# ADB-3020-CDV.net
KiCad netlist of a schematic drawn in EAGLE
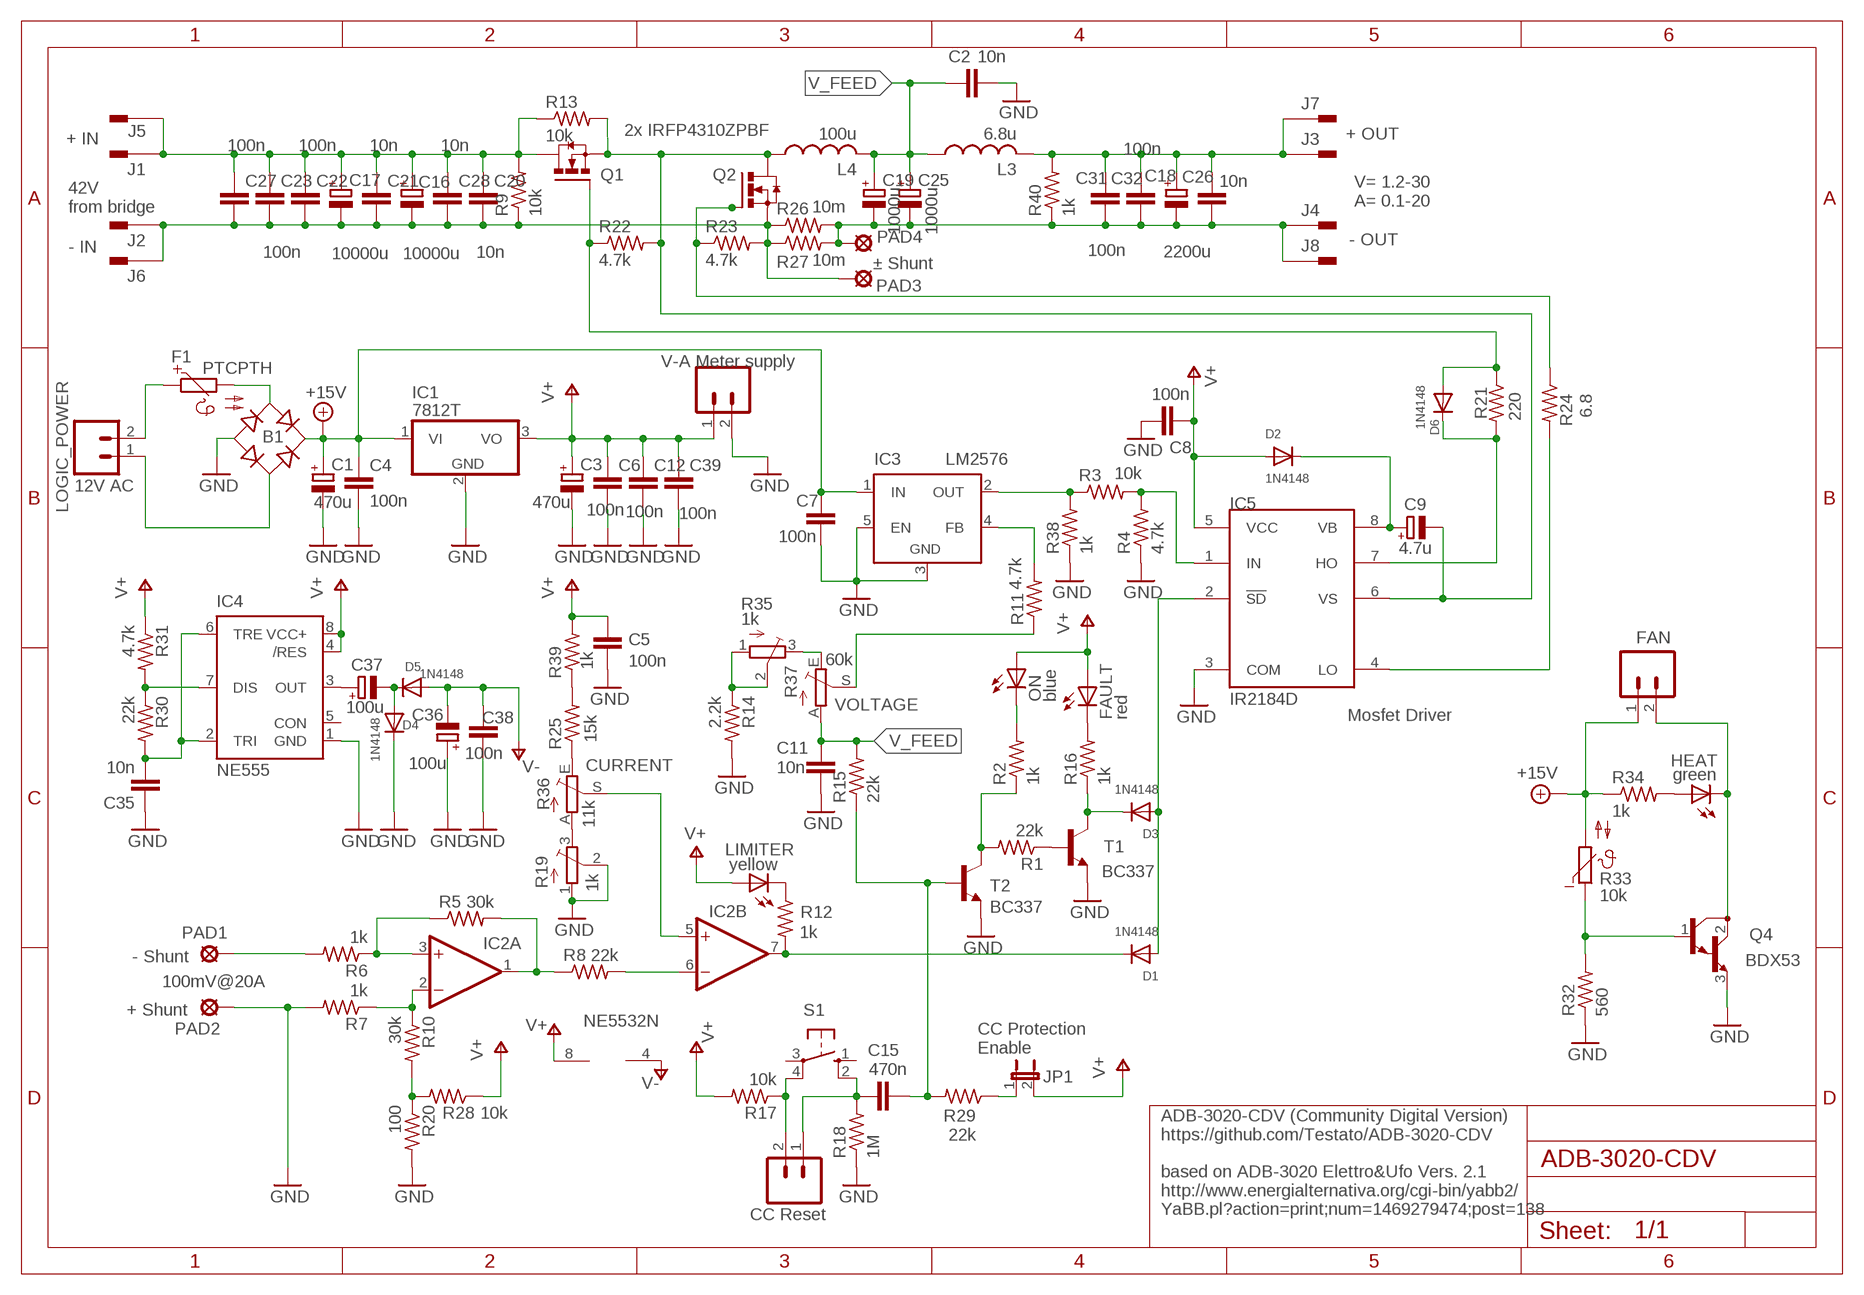
[diagram p0: schematic, sheet 1]

(export (version "E")
  (design (tool "Eeschema 10.0.6"))
  (components
    (comp (ref "B1")
      (value "RECTIFIER-RB1A")
      (footprint "eagle-import:RB1A")
      (libsource (lib "eagle-import") (part "RECTIFIER-RB1A"))
    )
    (comp (ref "C1")
      (value "470u")
      (footprint "eagle-import:E2-5")
      (libsource (lib "eagle-import") (part "CPOL-EUE2-5"))
    )
    (comp (ref "C2")
      (value "10n")
      (footprint "eagle-import:C2.5-2")
      (libsource (lib "eagle-import") (part "C2.5/2"))
    )
    (comp (ref "C3")
      (value "470u")
      (footprint "eagle-import:E2-5")
      (libsource (lib "eagle-import") (part "CPOL-EUE2-5"))
    )
    (comp (ref "C4")
      (value "100n")
      (footprint "eagle-import:C2.5-2")
      (libsource (lib "eagle-import") (part "C2.5/2"))
    )
    (comp (ref "C5")
      (value "100n")
      (footprint "eagle-import:C2.5-2")
      (libsource (lib "eagle-import") (part "C2.5/2"))
    )
    (comp (ref "C6")
      (value "100n")
      (footprint "eagle-import:C2.5-2")
      (libsource (lib "eagle-import") (part "C2.5/2"))
    )
    (comp (ref "C7")
      (value "100n")
      (footprint "eagle-import:C2.5-2")
      (libsource (lib "eagle-import") (part "C2.5/2"))
    )
    (comp (ref "C8")
      (value "100n")
      (footprint "eagle-import:C2.5-2")
      (libsource (lib "eagle-import") (part "C2.5/2"))
    )
    (comp (ref "C9")
      (value "4.7u")
      (footprint "eagle-import:E2-5")
      (libsource (lib "eagle-import") (part "CPOL-EUE2-5"))
    )
    (comp (ref "C11")
      (value "10n")
      (footprint "eagle-import:C2.5-2")
      (libsource (lib "eagle-import") (part "C2.5/2"))
    )
    (comp (ref "C12")
      (value "100n")
      (footprint "eagle-import:C2.5-2")
      (libsource (lib "eagle-import") (part "C2.5/2"))
    )
    (comp (ref "C15")
      (value "470n")
      (footprint "eagle-import:C2.5-2")
      (libsource (lib "eagle-import") (part "C2.5/2"))
    )
    (comp (ref "C16")
      (value "10000u")
      (footprint "eagle-import:E2-5")
      (libsource (lib "eagle-import") (part "CPOL-EUE2-5"))
    )
    (comp (ref "C17")
      (value "10000u")
      (footprint "eagle-import:E2-5")
      (libsource (lib "eagle-import") (part "CPOL-EUE2-5"))
    )
    (comp (ref "C18")
      (value "2200u")
      (footprint "eagle-import:E2-5")
      (libsource (lib "eagle-import") (part "CPOL-EUE2-5"))
    )
    (comp (ref "C19")
      (value "1000u")
      (footprint "eagle-import:E2-5")
      (libsource (lib "eagle-import") (part "CPOL-EUE2-5"))
    )
    (comp (ref "C20")
      (value "10n")
      (footprint "eagle-import:C2.5-2")
      (libsource (lib "eagle-import") (part "C2.5/2"))
    )
    (comp (ref "C21")
      (value "10n")
      (footprint "eagle-import:C2.5-2")
      (libsource (lib "eagle-import") (part "C2.5/2"))
    )
    (comp (ref "C22")
      (value "100n")
      (footprint "eagle-import:C2.5-2")
      (libsource (lib "eagle-import") (part "C2.5/2"))
    )
    (comp (ref "C23")
      (value "100n")
      (footprint "eagle-import:C2.5-2")
      (libsource (lib "eagle-import") (part "C2.5/2"))
    )
    (comp (ref "C25")
      (value "1000u")
      (footprint "eagle-import:E2-5")
      (libsource (lib "eagle-import") (part "CPOL-EUE2-5"))
    )
    (comp (ref "C26")
      (value "10n")
      (footprint "eagle-import:C2.5-2")
      (libsource (lib "eagle-import") (part "C2.5/2"))
    )
    (comp (ref "C27")
      (value "100n")
      (footprint "eagle-import:C2.5-2")
      (libsource (lib "eagle-import") (part "C2.5/2"))
    )
    (comp (ref "C28")
      (value "10n")
      (footprint "eagle-import:C2.5-2")
      (libsource (lib "eagle-import") (part "C2.5/2"))
    )
    (comp (ref "C31")
      (value "100n")
      (footprint "eagle-import:C2.5-2")
      (libsource (lib "eagle-import") (part "C2.5/2"))
    )
    (comp (ref "C32")
      (value "100n")
      (footprint "eagle-import:C2.5-2")
      (libsource (lib "eagle-import") (part "C2.5/2"))
    )
    (comp (ref "C35")
      (value "10n")
      (footprint "eagle-import:C2.5-2")
      (libsource (lib "eagle-import") (part "C2.5/2"))
    )
    (comp (ref "C36")
      (value "100u")
      (footprint "eagle-import:E2-5")
      (libsource (lib "eagle-import") (part "CPOL-EUE2-5"))
    )
    (comp (ref "C37")
      (value "100u")
      (footprint "eagle-import:E2-5")
      (libsource (lib "eagle-import") (part "CPOL-EUE2-5"))
    )
    (comp (ref "C38")
      (value "100n")
      (footprint "eagle-import:C2.5-2")
      (libsource (lib "eagle-import") (part "C2.5/2"))
    )
    (comp (ref "C39")
      (value "100n")
      (footprint "eagle-import:C2.5-2")
      (libsource (lib "eagle-import") (part "C2.5/2"))
    )
    (comp (ref "D1")
      (value "1N4148")
      (footprint "eagle-import:DO-1N4148")
      (libsource (lib "eagle-import") (part "DIODEDO-1N4148"))
    )
    (comp (ref "D2")
      (value "1N4148")
      (footprint "eagle-import:DO-1N4148")
      (libsource (lib "eagle-import") (part "DIODEDO-1N4148"))
    )
    (comp (ref "D3")
      (value "1N4148")
      (footprint "eagle-import:DO-1N4148")
      (libsource (lib "eagle-import") (part "DIODEDO-1N4148"))
    )
    (comp (ref "D4")
      (value "1N4148")
      (footprint "eagle-import:DO-1N4148")
      (libsource (lib "eagle-import") (part "DIODEDO-1N4148"))
    )
    (comp (ref "D5")
      (value "1N4148")
      (footprint "eagle-import:DO-1N4148")
      (libsource (lib "eagle-import") (part "DIODEDO-1N4148"))
    )
    (comp (ref "D6")
      (value "1N4148")
      (footprint "eagle-import:DO-1N4148")
      (libsource (lib "eagle-import") (part "DIODEDO-1N4148"))
    )
    (comp (ref "F1")
      (value "PTCPTH")
      (footprint "eagle-import:P660")
      (libsource (lib "eagle-import") (part "PTC660"))
    )
    (comp (ref "FAN")
      (value "fan")
      (footprint "eagle-import:02PA")
      (libsource (lib "eagle-import") (part "MA02"))
    )
    (comp (ref "FAULT")
      (value "red")
      (footprint "eagle-import:LED3MM")
      (libsource (lib "eagle-import") (part "LED3MM"))
    )
    (comp (ref "HEAT")
      (value "green")
      (footprint "eagle-import:LED3MM")
      (libsource (lib "eagle-import") (part "LED3MM"))
    )
    (comp (ref "IC1")
      (value "7812T")
      (footprint "eagle-import:TO220H")
      (libsource (lib "eagle-import") (part "78T12"))
    )
    (comp (ref "IC2")
      (value "NE5532N")
      (footprint "eagle-import:DIL08")
      (libsource (lib "eagle-import") (part "NE5532N"))
    )
    (comp (ref "IC3")
      (value "LM2576")
      (footprint "eagle-import:TO220-52")
      (libsource (lib "eagle-import") (part "LM2596TH"))
    )
    (comp (ref "IC4")
      (value "NE555")
      (footprint "eagle-import:DIL-08")
      (fields (field (name "MF") "Arrow Electronics") (field (name "MPN") "NE555N"))
      (libsource (lib "eagle-import") (part "NE555"))
    )
    (comp (ref "IC5")
      (value "IR2184D")
      (footprint "eagle-import:DIL08")
      (libsource (lib "eagle-import") (part "IR2184D"))
    )
    (comp (ref "J1")
      (value "+ IN")
      (footprint "eagle-import:F061.040")
      (libsource (lib "eagle-import") (part "PIN2F061.040"))
    )
    (comp (ref "J2")
      (value "- IN")
      (footprint "eagle-import:F061.040")
      (libsource (lib "eagle-import") (part "PIN2F061.040"))
    )
    (comp (ref "J3")
      (value "+ OUT")
      (footprint "eagle-import:F061.040")
      (libsource (lib "eagle-import") (part "PIN2F061.040"))
    )
    (comp (ref "J4")
      (value "PIN2F061.040")
      (footprint "eagle-import:F061.040")
      (libsource (lib "eagle-import") (part "PIN2F061.040"))
    )
    (comp (ref "J5")
      (value "+ IN")
      (footprint "eagle-import:F061.040")
      (libsource (lib "eagle-import") (part "PIN2F061.040"))
    )
    (comp (ref "J6")
      (value "- IN")
      (footprint "eagle-import:F061.040")
      (libsource (lib "eagle-import") (part "PIN2F061.040"))
    )
    (comp (ref "J7")
      (value "PIN2F061.040")
      (footprint "eagle-import:F061.040")
      (libsource (lib "eagle-import") (part "PIN2F061.040"))
    )
    (comp (ref "J8")
      (value "- OUT")
      (footprint "eagle-import:F061.040")
      (libsource (lib "eagle-import") (part "PIN2F061.040"))
    )
    (comp (ref "JP1")
      (value "jp1")
      (footprint "eagle-import:JP1")
      (libsource (lib "eagle-import") (part "JP1E"))
    )
    (comp (ref "L3")
      (value "6.8u")
      (footprint "eagle-import:6000")
      (libsource (lib "eagle-import") (part "L"))
    )
    (comp (ref "L4")
      (value "100u")
      (footprint "eagle-import:6000")
      (libsource (lib "eagle-import") (part "L"))
    )
    (comp (ref "LIMITER")
      (value "yellow")
      (footprint "eagle-import:LED3MM")
      (libsource (lib "eagle-import") (part "LED3MM"))
    )
    (comp (ref "LOGIC_POWER")
      (value "12V AC")
      (footprint "eagle-import:02PA")
      (libsource (lib "eagle-import") (part "MA02"))
    )
    (comp (ref "ON")
      (value "blue")
      (footprint "eagle-import:LED3MM")
      (libsource (lib "eagle-import") (part "LED3MM"))
    )
    (comp (ref "PAD1")
      (value "LSP13")
      (footprint "eagle-import:LSP13")
      (libsource (lib "eagle-import") (part "LSP13"))
    )
    (comp (ref "PAD2")
      (value "LSP13")
      (footprint "eagle-import:LSP13")
      (libsource (lib "eagle-import") (part "LSP13"))
    )
    (comp (ref "PAD3")
      (value "LSP13")
      (footprint "eagle-import:LSP13")
      (libsource (lib "eagle-import") (part "LSP13"))
    )
    (comp (ref "PAD4")
      (value "LSP13")
      (footprint "eagle-import:LSP13")
      (libsource (lib "eagle-import") (part "LSP13"))
    )
    (comp (ref "Q1")
      (value "IRFP240-H")
      (footprint "eagle-import:TO247BH")
      (libsource (lib "eagle-import") (part "IRFP240-H"))
    )
    (comp (ref "Q2")
      (value "IRFP240-H")
      (footprint "eagle-import:TO247BH")
      (libsource (lib "eagle-import") (part "IRFP240-H"))
    )
    (comp (ref "Q4")
      (value "BDX53")
      (footprint "eagle-import:TO220")
      (libsource (lib "eagle-import") (part "BDX53"))
    )
    (comp (ref "R1")
      (value "22k")
      (footprint "eagle-import:0204_5")
      (libsource (lib "eagle-import") (part "R-US_0204/5"))
    )
    (comp (ref "R2")
      (value "1k")
      (footprint "eagle-import:0204_5")
      (libsource (lib "eagle-import") (part "R-US_0204/5"))
    )
    (comp (ref "R3")
      (value "10k")
      (footprint "eagle-import:0204_5")
      (libsource (lib "eagle-import") (part "R-US_0204/5"))
    )
    (comp (ref "R4")
      (value "4.7k")
      (footprint "eagle-import:0204_5")
      (libsource (lib "eagle-import") (part "R-US_0204/5"))
    )
    (comp (ref "R5")
      (value "30k")
      (footprint "eagle-import:0204_5")
      (libsource (lib "eagle-import") (part "R-US_0204/5"))
    )
    (comp (ref "R6")
      (value "1k")
      (footprint "eagle-import:0204_5")
      (libsource (lib "eagle-import") (part "R-US_0204/5"))
    )
    (comp (ref "R7")
      (value "1k")
      (footprint "eagle-import:0204_5")
      (libsource (lib "eagle-import") (part "R-US_0204/5"))
    )
    (comp (ref "R8")
      (value "22k")
      (footprint "eagle-import:0204_5")
      (libsource (lib "eagle-import") (part "R-US_0204/5"))
    )
    (comp (ref "R9")
      (value "10k")
      (footprint "eagle-import:0204_5")
      (libsource (lib "eagle-import") (part "R-US_0204/5"))
    )
    (comp (ref "R10")
      (value "30k")
      (footprint "eagle-import:0204_5")
      (libsource (lib "eagle-import") (part "R-US_0204/5"))
    )
    (comp (ref "R11")
      (value "4.7k")
      (footprint "eagle-import:0204_5")
      (libsource (lib "eagle-import") (part "R-US_0204/5"))
    )
    (comp (ref "R12")
      (value "1k")
      (footprint "eagle-import:0204_5")
      (libsource (lib "eagle-import") (part "R-US_0204/5"))
    )
    (comp (ref "R13")
      (value "10k")
      (footprint "eagle-import:0204_5")
      (libsource (lib "eagle-import") (part "R-US_0204/5"))
    )
    (comp (ref "R14")
      (value "2.2k")
      (footprint "eagle-import:0204_5")
      (libsource (lib "eagle-import") (part "R-US_0204/5"))
    )
    (comp (ref "R15")
      (value "22k")
      (footprint "eagle-import:0204_5")
      (libsource (lib "eagle-import") (part "R-US_0204/5"))
    )
    (comp (ref "R16")
      (value "1k")
      (footprint "eagle-import:0204_5")
      (libsource (lib "eagle-import") (part "R-US_0204/5"))
    )
    (comp (ref "R17")
      (value "10k")
      (footprint "eagle-import:0204_5")
      (libsource (lib "eagle-import") (part "R-US_0204/5"))
    )
    (comp (ref "R18")
      (value "1M")
      (footprint "eagle-import:0204_5")
      (libsource (lib "eagle-import") (part "R-US_0204/5"))
    )
    (comp (ref "R19")
      (value "1k")
      (footprint "eagle-import:TRIM-3386")
      (libsource (lib "eagle-import") (part "TRIMPOT3386"))
    )
    (comp (ref "R20")
      (value "100")
      (footprint "eagle-import:0204_5")
      (libsource (lib "eagle-import") (part "R-US_0204/5"))
    )
    (comp (ref "R21")
      (value "220")
      (footprint "eagle-import:0204_5")
      (libsource (lib "eagle-import") (part "R-US_0204/5"))
    )
    (comp (ref "R22")
      (value "4.7k")
      (footprint "eagle-import:0204_5")
      (libsource (lib "eagle-import") (part "R-US_0204/5"))
    )
    (comp (ref "R23")
      (value "4.7k")
      (footprint "eagle-import:0204_5")
      (libsource (lib "eagle-import") (part "R-US_0204/5"))
    )
    (comp (ref "R24")
      (value "6.8")
      (footprint "eagle-import:0204_5")
      (libsource (lib "eagle-import") (part "R-US_0204/5"))
    )
    (comp (ref "R25")
      (value "15k")
      (footprint "eagle-import:0204_5")
      (libsource (lib "eagle-import") (part "R-US_0204/5"))
    )
    (comp (ref "R26")
      (value "10m")
      (footprint "eagle-import:0204_5")
      (libsource (lib "eagle-import") (part "R-US_0204/5"))
    )
    (comp (ref "R27")
      (value "10m")
      (footprint "eagle-import:0204_5")
      (libsource (lib "eagle-import") (part "R-US_0204/5"))
    )
    (comp (ref "R28")
      (value "10k")
      (footprint "eagle-import:0204_5")
      (libsource (lib "eagle-import") (part "R-US_0204/5"))
    )
    (comp (ref "R29")
      (value "22k")
      (footprint "eagle-import:0204_5")
      (libsource (lib "eagle-import") (part "R-US_0204/5"))
    )
    (comp (ref "R30")
      (value "22k")
      (footprint "eagle-import:0204_5")
      (libsource (lib "eagle-import") (part "R-US_0204/5"))
    )
    (comp (ref "R31")
      (value "4.7k")
      (footprint "eagle-import:0204_5")
      (libsource (lib "eagle-import") (part "R-US_0204/5"))
    )
    (comp (ref "R32")
      (value "560")
      (footprint "eagle-import:0204_5")
      (libsource (lib "eagle-import") (part "R-US_0204/5"))
    )
    (comp (ref "R33")
      (value "10k")
      (footprint "eagle-import:P640")
      (libsource (lib "eagle-import") (part "NTC640"))
    )
    (comp (ref "R34")
      (value "1k")
      (footprint "eagle-import:0204_5")
      (libsource (lib "eagle-import") (part "R-US_0204/5"))
    )
    (comp (ref "R35")
      (value "1k")
      (footprint "eagle-import:TRIM-3386")
      (libsource (lib "eagle-import") (part "TRIMPOT3386"))
    )
    (comp (ref "R36")
      (value "11k")
      (footprint "eagle-import:S64YW")
      (libsource (lib "eagle-import") (part "TRIM_1234-S64YW"))
    )
    (comp (ref "R37")
      (value "60k")
      (footprint "eagle-import:S64YW")
      (libsource (lib "eagle-import") (part "TRIM_1234-S64YW"))
    )
    (comp (ref "R38")
      (value "1k")
      (footprint "eagle-import:0204_5")
      (libsource (lib "eagle-import") (part "R-US_0204/5"))
    )
    (comp (ref "R39")
      (value "1k")
      (footprint "eagle-import:0204_5")
      (libsource (lib "eagle-import") (part "R-US_0204/5"))
    )
    (comp (ref "R40")
      (value "1k")
      (footprint "eagle-import:0204_5")
      (libsource (lib "eagle-import") (part "R-US_0204/5"))
    )
    (comp (ref "RESET")
      (value "CC Reset")
      (footprint "eagle-import:02PA")
      (libsource (lib "eagle-import") (part "MA02"))
    )
    (comp (ref "S1")
      (value "CC Reset")
      (footprint "eagle-import:B3F-40XX")
      (fields (field (name "MF") "OMRON COMPONENTS USA") (field (name "MPN") "B3F-4000"))
      (libsource (lib "eagle-import") (part "40-XX"))
    )
    (comp (ref "T1")
      (value "BC337")
      (footprint "eagle-import:TO92")
      (libsource (lib "eagle-import") (part "BC337"))
    )
    (comp (ref "T2")
      (value "BC337")
      (footprint "eagle-import:TO92")
      (libsource (lib "eagle-import") (part "BC337"))
    )
    (comp (ref "V-A_METER_SUPPLY")
      (value "V-A Meter supply")
      (footprint "eagle-import:02PA")
      (libsource (lib "eagle-import") (part "MA02"))
    )
  )
  (nets
    (net (code "1") (name "+15V") (class "Default")
      (node (ref "B1") (pin "+") (pinfunction "+_+") (pintype "passive"))
      (node (ref "C1") (pin "+") (pinfunction "+_+") (pintype "passive"))
      (node (ref "C4") (pin "1") (pinfunction "1_1") (pintype "passive"))
      (node (ref "C7") (pin "1") (pinfunction "1_1") (pintype "passive"))
      (node (ref "FAN") (pin "1") (pinfunction "1_1") (pintype "passive"))
      (node (ref "IC1") (pin "1") (pinfunction "VI_1") (pintype "input"))
      (node (ref "IC3") (pin "1") (pinfunction "IN_1") (pintype "input"))
      (node (ref "R33") (pin "2") (pinfunction "2_2") (pintype "passive"))
      (node (ref "R34") (pin "1") (pinfunction "1_1") (pintype "passive"))
    )
    (net (code "2") (name "GND") (class "Default")
      (node (ref "B1") (pin "-") (pinfunction "-_-") (pintype "passive"))
      (node (ref "C1") (pin "-") (pinfunction "-_-") (pintype "passive"))
      (node (ref "C11") (pin "2") (pinfunction "2_2") (pintype "passive"))
      (node (ref "C12") (pin "2") (pinfunction "2_2") (pintype "passive"))
      (node (ref "C2") (pin "2") (pinfunction "2_2") (pintype "passive"))
      (node (ref "C3") (pin "-") (pinfunction "-_-") (pintype "passive"))
      (node (ref "C35") (pin "1") (pinfunction "1_1") (pintype "passive"))
      (node (ref "C36") (pin "+") (pinfunction "+_+") (pintype "passive"))
      (node (ref "C38") (pin "1") (pinfunction "1_1") (pintype "passive"))
      (node (ref "C39") (pin "2") (pinfunction "2_2") (pintype "passive"))
      (node (ref "C4") (pin "2") (pinfunction "2_2") (pintype "passive"))
      (node (ref "C5") (pin "1") (pinfunction "1_1") (pintype "passive"))
      (node (ref "C6") (pin "2") (pinfunction "2_2") (pintype "passive"))
      (node (ref "C7") (pin "2") (pinfunction "2_2") (pintype "passive"))
      (node (ref "C8") (pin "2") (pinfunction "2_2") (pintype "passive"))
      (node (ref "D4") (pin "C") (pinfunction "C_C") (pintype "passive"))
      (node (ref "IC1") (pin "2") (pinfunction "GND_2") (pintype "passive"))
      (node (ref "IC3") (pin "3") (pinfunction "GND_3") (pintype "power_in"))
      (node (ref "IC3") (pin "5") (pinfunction "EN_5") (pintype "input"))
      (node (ref "IC4") (pin "1") (pinfunction "GND_1") (pintype "power_in"))
      (node (ref "IC5") (pin "3") (pinfunction "COM_3") (pintype "power_in"))
      (node (ref "PAD2") (pin "MP") (pinfunction "MP_MP") (pintype "passive"))
      (node (ref "Q4") (pin "3") (pinfunction "E_3") (pintype "passive"))
      (node (ref "R14") (pin "2") (pinfunction "2_2") (pintype "passive"))
      (node (ref "R18") (pin "1") (pinfunction "1_1") (pintype "passive"))
      (node (ref "R19") (pin "1") (pinfunction "A_1") (pintype "passive"))
      (node (ref "R19") (pin "2") (pinfunction "S_2") (pintype "passive"))
      (node (ref "R20") (pin "2") (pinfunction "2_2") (pintype "passive"))
      (node (ref "R32") (pin "1") (pinfunction "1_1") (pintype "passive"))
      (node (ref "R38") (pin "1") (pinfunction "1_1") (pintype "passive"))
      (node (ref "R4") (pin "1") (pinfunction "1_1") (pintype "passive"))
      (node (ref "R7") (pin "2") (pinfunction "2_2") (pintype "passive"))
      (node (ref "T1") (pin "1") (pinfunction "E_1") (pintype "passive"))
      (node (ref "T2") (pin "1") (pinfunction "E_1") (pintype "passive"))
      (node (ref "V-A_METER_SUPPLY") (pin "2") (pinfunction "2_2") (pintype "passive"))
    )
    (net (code "3") (name "Net-(B1-PadAC1)") (class "Default")
      (node (ref "B1") (pin "AC1") (pinfunction "AC1_AC1") (pintype "passive"))
      (node (ref "F1") (pin "2") (pinfunction "2_2") (pintype "passive"))
    )
    (net (code "4") (name "Net-(B1-PadAC2)") (class "Default")
      (node (ref "B1") (pin "AC2") (pinfunction "AC2_AC2") (pintype "passive"))
      (node (ref "LOGIC_POWER") (pin "1") (pinfunction "1_1") (pintype "passive"))
    )
    (net (code "5") (name "Net-(C16-Pad+)") (class "Default")
      (node (ref "C16") (pin "+") (pinfunction "+_+") (pintype "passive"))
      (node (ref "C17") (pin "+") (pinfunction "+_+") (pintype "passive"))
      (node (ref "C20") (pin "1") (pinfunction "1_1") (pintype "passive"))
      (node (ref "C21") (pin "1") (pinfunction "1_1") (pintype "passive"))
      (node (ref "C22") (pin "1") (pinfunction "1_1") (pintype "passive"))
      (node (ref "C23") (pin "1") (pinfunction "1_1") (pintype "passive"))
      (node (ref "C27") (pin "1") (pinfunction "1_1") (pintype "passive"))
      (node (ref "C28") (pin "1") (pinfunction "1_1") (pintype "passive"))
      (node (ref "J1") (pin "A1") (pinfunction "1_A1") (pintype "passive"))
      (node (ref "J1") (pin "A2") (pinfunction "1_A2") (pintype "passive"))
      (node (ref "J5") (pin "A1") (pinfunction "1_A1") (pintype "passive"))
      (node (ref "J5") (pin "A2") (pinfunction "1_A2") (pintype "passive"))
      (node (ref "Q1") (pin "D") (pinfunction "D_D") (pintype "passive"))
      (node (ref "R13") (pin "1") (pinfunction "1_1") (pintype "passive"))
      (node (ref "R9") (pin "2") (pinfunction "2_2") (pintype "passive"))
    )
    (net (code "6") (name "Net-(C16-Pad-)") (class "Default")
      (node (ref "C16") (pin "-") (pinfunction "-_-") (pintype "passive"))
      (node (ref "C17") (pin "-") (pinfunction "-_-") (pintype "passive"))
      (node (ref "C20") (pin "2") (pinfunction "2_2") (pintype "passive"))
      (node (ref "C21") (pin "2") (pinfunction "2_2") (pintype "passive"))
      (node (ref "C22") (pin "2") (pinfunction "2_2") (pintype "passive"))
      (node (ref "C23") (pin "2") (pinfunction "2_2") (pintype "passive"))
      (node (ref "C27") (pin "2") (pinfunction "2_2") (pintype "passive"))
      (node (ref "C28") (pin "2") (pinfunction "2_2") (pintype "passive"))
      (node (ref "J2") (pin "A1") (pinfunction "1_A1") (pintype "passive"))
      (node (ref "J2") (pin "A2") (pinfunction "1_A2") (pintype "passive"))
      (node (ref "J6") (pin "A1") (pinfunction "1_A1") (pintype "passive"))
      (node (ref "J6") (pin "A2") (pinfunction "1_A2") (pintype "passive"))
      (node (ref "PAD3") (pin "MP") (pinfunction "MP_MP") (pintype "passive"))
      (node (ref "Q2") (pin "S") (pinfunction "S_S") (pintype "passive"))
      (node (ref "R23") (pin "2") (pinfunction "2_2") (pintype "passive"))
      (node (ref "R26") (pin "1") (pinfunction "1_1") (pintype "passive"))
      (node (ref "R27") (pin "1") (pinfunction "1_1") (pintype "passive"))
      (node (ref "R9") (pin "1") (pinfunction "1_1") (pintype "passive"))
    )
    (net (code "7") (name "Net-(C18-Pad+)") (class "Default")
      (node (ref "C18") (pin "+") (pinfunction "+_+") (pintype "passive"))
      (node (ref "C26") (pin "1") (pinfunction "1_1") (pintype "passive"))
      (node (ref "C31") (pin "1") (pinfunction "1_1") (pintype "passive"))
      (node (ref "C32") (pin "1") (pinfunction "1_1") (pintype "passive"))
      (node (ref "J3") (pin "A1") (pinfunction "1_A1") (pintype "passive"))
      (node (ref "J3") (pin "A2") (pinfunction "1_A2") (pintype "passive"))
      (node (ref "J7") (pin "A1") (pinfunction "1_A1") (pintype "passive"))
      (node (ref "J7") (pin "A2") (pinfunction "1_A2") (pintype "passive"))
      (node (ref "L3") (pin "2") (pinfunction "2_2") (pintype "passive"))
      (node (ref "R40") (pin "2") (pinfunction "2_2") (pintype "passive"))
    )
    (net (code "8") (name "Net-(C18-Pad-)") (class "Default")
      (node (ref "C18") (pin "-") (pinfunction "-_-") (pintype "passive"))
      (node (ref "C19") (pin "-") (pinfunction "-_-") (pintype "passive"))
      (node (ref "C25") (pin "-") (pinfunction "-_-") (pintype "passive"))
      (node (ref "C26") (pin "2") (pinfunction "2_2") (pintype "passive"))
      (node (ref "C31") (pin "2") (pinfunction "2_2") (pintype "passive"))
      (node (ref "C32") (pin "2") (pinfunction "2_2") (pintype "passive"))
      (node (ref "J4") (pin "A1") (pinfunction "1_A1") (pintype "passive"))
      (node (ref "J4") (pin "A2") (pinfunction "1_A2") (pintype "passive"))
      (node (ref "J8") (pin "A1") (pinfunction "1_A1") (pintype "passive"))
      (node (ref "J8") (pin "A2") (pinfunction "1_A2") (pintype "passive"))
      (node (ref "PAD4") (pin "MP") (pinfunction "MP_MP") (pintype "passive"))
      (node (ref "R26") (pin "2") (pinfunction "2_2") (pintype "passive"))
      (node (ref "R27") (pin "2") (pinfunction "2_2") (pintype "passive"))
      (node (ref "R40") (pin "1") (pinfunction "1_1") (pintype "passive"))
    )
    (net (code "9") (name "Net-(C37-Pad-)") (class "Default")
      (node (ref "C37") (pin "-") (pinfunction "-_-") (pintype "passive"))
      (node (ref "D4") (pin "A") (pinfunction "A_A") (pintype "passive"))
      (node (ref "D5") (pin "C") (pinfunction "C_C") (pintype "passive"))
    )
    (net (code "10") (name "Net-(D6-PadA)") (class "Default")
      (node (ref "D6") (pin "A") (pinfunction "A_A") (pintype "passive"))
      (node (ref "Q1") (pin "G") (pinfunction "G_G") (pintype "passive"))
      (node (ref "R21") (pin "1") (pinfunction "1_1") (pintype "passive"))
      (node (ref "R22") (pin "1") (pinfunction "1_1") (pintype "passive"))
    )
    (net (code "11") (name "Net-(F1-Pad1)") (class "Default")
      (node (ref "F1") (pin "1") (pinfunction "1_1") (pintype "passive"))
      (node (ref "LOGIC_POWER") (pin "2") (pinfunction "2_2") (pintype "passive"))
    )
    (net (code "12") (name "Net-(FAULT-C)") (class "Default")
      (node (ref "FAULT") (pin "K") (pinfunction "C_K") (pintype "passive"))
      (node (ref "R16") (pin "2") (pinfunction "2_2") (pintype "passive"))
    )
    (net (code "13") (name "Net-(HEAT-C)") (class "Default")
      (node (ref "FAN") (pin "2") (pinfunction "2_2") (pintype "passive"))
      (node (ref "HEAT") (pin "K") (pinfunction "C_K") (pintype "passive"))
      (node (ref "Q4") (pin "2") (pinfunction "C_2") (pintype "passive"))
    )
    (net (code "14") (name "Net-(HEAT-PadA)") (class "Default")
      (node (ref "HEAT") (pin "A") (pinfunction "A_A") (pintype "passive"))
      (node (ref "R34") (pin "2") (pinfunction "2_2") (pintype "passive"))
    )
    (net (code "15") (name "Net-(IC2A-+IN)") (class "Default")
      (node (ref "IC2") (pin "3") (pinfunction "+IN_3") (pintype "input"))
      (node (ref "R5") (pin "1") (pinfunction "1_1") (pintype "passive"))
      (node (ref "R6") (pin "1") (pinfunction "1_1") (pintype "passive"))
    )
    (net (code "16") (name "Net-(IC2A--IN)") (class "Default")
      (node (ref "IC2") (pin "2") (pinfunction "-IN_2") (pintype "input"))
      (node (ref "R10") (pin "1") (pinfunction "1_1") (pintype "passive"))
      (node (ref "R7") (pin "1") (pinfunction "1_1") (pintype "passive"))
    )
    (net (code "17") (name "Net-(IC2A-OUT)") (class "Default")
      (node (ref "IC2") (pin "1") (pinfunction "OUT_1") (pintype "output"))
      (node (ref "R5") (pin "2") (pinfunction "2_2") (pintype "passive"))
      (node (ref "R8") (pin "1") (pinfunction "1_1") (pintype "passive"))
    )
    (net (code "18") (name "Net-(IC2B-+IN)") (class "Default")
      (node (ref "IC2") (pin "5") (pinfunction "+IN_5") (pintype "input"))
      (node (ref "R36") (pin "S") (pinfunction "S_S") (pintype "passive"))
    )
    (net (code "19") (name "Net-(IC2B--IN)") (class "Default")
      (node (ref "IC2") (pin "6") (pinfunction "-IN_6") (pintype "input"))
      (node (ref "R8") (pin "2") (pinfunction "2_2") (pintype "passive"))
    )
    (net (code "20") (name "Net-(IC2B-OUT)") (class "Default")
      (node (ref "D1") (pin "C") (pinfunction "C_C") (pintype "passive"))
      (node (ref "IC2") (pin "7") (pinfunction "OUT_7") (pintype "output"))
      (node (ref "R12") (pin "2") (pinfunction "2_2") (pintype "passive"))
    )
    (net (code "21") (name "Net-(IC3-FB)") (class "Default")
      (node (ref "IC3") (pin "4") (pinfunction "FB_4") (pintype "input"))
      (node (ref "R11") (pin "2") (pinfunction "2_2") (pintype "passive"))
    )
    (net (code "22") (name "Net-(IC3-OUT)") (class "Default")
      (node (ref "IC3") (pin "2") (pinfunction "OUT_2") (pintype "output"))
      (node (ref "R3") (pin "1") (pinfunction "1_1") (pintype "passive"))
      (node (ref "R38") (pin "2") (pinfunction "2_2") (pintype "passive"))
    )
    (net (code "23") (name "Net-(IC4-DIS)") (class "Default")
      (node (ref "IC4") (pin "7") (pinfunction "DIS_7") (pintype "input"))
      (node (ref "R30") (pin "1") (pinfunction "1_1") (pintype "passive"))
      (node (ref "R31") (pin "2") (pinfunction "2_2") (pintype "passive"))
    )
    (net (code "24") (name "Net-(IC4-OUT)") (class "Default")
      (node (ref "C37") (pin "+") (pinfunction "+_+") (pintype "passive"))
      (node (ref "IC4") (pin "3") (pinfunction "OUT_3") (pintype "output"))
    )
    (net (code "25") (name "Net-(IC4-TRE)") (class "Default")
      (node (ref "C35") (pin "2") (pinfunction "2_2") (pintype "passive"))
      (node (ref "IC4") (pin "2") (pinfunction "TRI_2") (pintype "input"))
      (node (ref "IC4") (pin "6") (pinfunction "TRE_6") (pintype "input"))
      (node (ref "R30") (pin "2") (pinfunction "2_2") (pintype "passive"))
    )
    (net (code "26") (name "Net-(IC5-HO)") (class "Default")
      (node (ref "D6") (pin "C") (pinfunction "C_C") (pintype "passive"))
      (node (ref "IC5") (pin "7") (pinfunction "HO_7") (pintype "output"))
      (node (ref "R21") (pin "2") (pinfunction "2_2") (pintype "passive"))
    )
    (net (code "27") (name "Net-(IC5-IN)") (class "Default")
      (node (ref "IC5") (pin "1") (pinfunction "IN_1") (pintype "input"))
      (node (ref "R3") (pin "2") (pinfunction "2_2") (pintype "passive"))
      (node (ref "R4") (pin "2") (pinfunction "2_2") (pintype "passive"))
    )
    (net (code "28") (name "Net-(IC5-LO)") (class "Default")
      (node (ref "IC5") (pin "4") (pinfunction "LO_4") (pintype "output"))
      (node (ref "R24") (pin "2") (pinfunction "2_2") (pintype "passive"))
    )
    (net (code "29") (name "Net-(IC5-VB)") (class "Default")
      (node (ref "C9") (pin "+") (pinfunction "+_+") (pintype "passive"))
      (node (ref "D2") (pin "C") (pinfunction "C_C") (pintype "passive"))
      (node (ref "IC5") (pin "8") (pinfunction "VB_8") (pintype "power_in"))
    )
    (net (code "30") (name "Net-(IC5-VS)") (class "Default")
      (node (ref "C9") (pin "-") (pinfunction "-_-") (pintype "passive"))
      (node (ref "IC5") (pin "6") (pinfunction "VS_6") (pintype "power_in"))
      (node (ref "L4") (pin "1") (pinfunction "1_1") (pintype "passive"))
      (node (ref "Q1") (pin "S") (pinfunction "S_S") (pintype "passive"))
      (node (ref "Q2") (pin "D") (pinfunction "D_D") (pintype "passive"))
      (node (ref "R13") (pin "2") (pinfunction "2_2") (pintype "passive"))
      (node (ref "R22") (pin "2") (pinfunction "2_2") (pintype "passive"))
    )
    (net (code "31") (name "Net-(IC5-~{SD})") (class "Default")
      (node (ref "D1") (pin "A") (pinfunction "A_A") (pintype "passive"))
      (node (ref "D3") (pin "A") (pinfunction "A_A") (pintype "passive"))
      (node (ref "IC5") (pin "2") (pinfunction "~{SD}_2") (pintype "input"))
    )
    (net (code "32") (name "Net-(JP1-Pad1)") (class "Default")
      (node (ref "JP1") (pin "1") (pinfunction "1_1") (pintype "passive"))
      (node (ref "R29") (pin "1") (pinfunction "1_1") (pintype "passive"))
    )
    (net (code "33") (name "Net-(LIMITER-C)") (class "Default")
      (node (ref "LIMITER") (pin "K") (pinfunction "C_K") (pintype "passive"))
      (node (ref "R12") (pin "1") (pinfunction "1_1") (pintype "passive"))
    )
    (net (code "34") (name "Net-(ON-C)") (class "Default")
      (node (ref "ON") (pin "K") (pinfunction "C_K") (pintype "passive"))
      (node (ref "R2") (pin "2") (pinfunction "2_2") (pintype "passive"))
    )
    (net (code "35") (name "Net-(PAD1-PadMP)") (class "Default")
      (node (ref "PAD1") (pin "MP") (pinfunction "MP_MP") (pintype "passive"))
      (node (ref "R6") (pin "2") (pinfunction "2_2") (pintype "passive"))
    )
    (net (code "36") (name "Net-(Q2-PadG)") (class "Default")
      (node (ref "Q2") (pin "G") (pinfunction "G_G") (pintype "passive"))
      (node (ref "R23") (pin "1") (pinfunction "1_1") (pintype "passive"))
      (node (ref "R24") (pin "1") (pinfunction "1_1") (pintype "passive"))
    )
    (net (code "37") (name "Net-(Q4-B)") (class "Default")
      (node (ref "Q4") (pin "1") (pinfunction "B_1") (pintype "passive"))
      (node (ref "R32") (pin "2") (pinfunction "2_2") (pintype "passive"))
      (node (ref "R33") (pin "1") (pinfunction "1_1") (pintype "passive"))
    )
    (net (code "38") (name "Net-(R10-Pad2)") (class "Default")
      (node (ref "R10") (pin "2") (pinfunction "2_2") (pintype "passive"))
      (node (ref "R20") (pin "1") (pinfunction "1_1") (pintype "passive"))
      (node (ref "R28") (pin "2") (pinfunction "2_2") (pintype "passive"))
    )
    (net (code "39") (name "Net-(R11-Pad1)") (class "Default")
      (node (ref "R11") (pin "1") (pinfunction "1_1") (pintype "passive"))
      (node (ref "R37") (pin "S") (pinfunction "S_S") (pintype "passive"))
    )
    (net (code "40") (name "Net-(R19-E)") (class "Default")
      (node (ref "R19") (pin "3") (pinfunction "E_3") (pintype "passive"))
      (node (ref "R36") (pin "A") (pinfunction "A_A") (pintype "passive"))
    )
    (net (code "41") (name "Net-(R25-Pad1)") (class "Default")
      (node (ref "R25") (pin "1") (pinfunction "1_1") (pintype "passive"))
      (node (ref "R36") (pin "E") (pinfunction "E_E") (pintype "passive"))
    )
    (net (code "42") (name "Net-(R25-Pad2)") (class "Default")
      (node (ref "R25") (pin "2") (pinfunction "2_2") (pintype "passive"))
      (node (ref "R39") (pin "1") (pinfunction "1_1") (pintype "passive"))
    )
    (net (code "43") (name "Net-(R35-A)") (class "Default")
      (node (ref "R14") (pin "1") (pinfunction "1_1") (pintype "passive"))
      (node (ref "R35") (pin "1") (pinfunction "A_1") (pintype "passive"))
      (node (ref "R35") (pin "2") (pinfunction "S_2") (pintype "passive"))
    )
    (net (code "44") (name "Net-(R35-E)") (class "Default")
      (node (ref "R35") (pin "3") (pinfunction "E_3") (pintype "passive"))
      (node (ref "R37") (pin "E") (pinfunction "E_E") (pintype "passive"))
    )
    (net (code "45") (name "Net-(S1-P1)") (class "Default")
      (node (ref "R17") (pin "1") (pinfunction "1_1") (pintype "passive"))
      (node (ref "RESET") (pin "2") (pinfunction "2_2") (pintype "passive"))
      (node (ref "S1") (pin "4") (pinfunction "P1_4") (pintype "passive"))
    )
    (net (code "46") (name "Net-(S1-S1)") (class "Default")
      (node (ref "C15") (pin "1") (pinfunction "1_1") (pintype "passive"))
      (node (ref "R18") (pin "2") (pinfunction "2_2") (pintype "passive"))
      (node (ref "RESET") (pin "1") (pinfunction "1_1") (pintype "passive"))
      (node (ref "S1") (pin "2") (pinfunction "S1_2") (pintype "passive"))
    )
    (net (code "47") (name "Net-(T1-B)") (class "Default")
      (node (ref "R1") (pin "1") (pinfunction "1_1") (pintype "passive"))
      (node (ref "T1") (pin "2") (pinfunction "B_2") (pintype "passive"))
    )
    (net (code "48") (name "Net-(T1-C)") (class "Default")
      (node (ref "D3") (pin "C") (pinfunction "C_C") (pintype "passive"))
      (node (ref "R16") (pin "1") (pinfunction "1_1") (pintype "passive"))
      (node (ref "T1") (pin "3") (pinfunction "C_3") (pintype "passive"))
    )
    (net (code "49") (name "Net-(T2-B)") (class "Default")
      (node (ref "C15") (pin "2") (pinfunction "2_2") (pintype "passive"))
      (node (ref "R15") (pin "1") (pinfunction "1_1") (pintype "passive"))
      (node (ref "R29") (pin "2") (pinfunction "2_2") (pintype "passive"))
      (node (ref "T2") (pin "2") (pinfunction "B_2") (pintype "passive"))
    )
    (net (code "50") (name "Net-(T2-C)") (class "Default")
      (node (ref "R1") (pin "2") (pinfunction "2_2") (pintype "passive"))
      (node (ref "R2") (pin "1") (pinfunction "1_1") (pintype "passive"))
      (node (ref "T2") (pin "3") (pinfunction "C_3") (pintype "passive"))
    )
    (net (code "51") (name "V+") (class "Default")
      (node (ref "C12") (pin "1") (pinfunction "1_1") (pintype "passive"))
      (node (ref "C3") (pin "+") (pinfunction "+_+") (pintype "passive"))
      (node (ref "C39") (pin "1") (pinfunction "1_1") (pintype "passive"))
      (node (ref "C5") (pin "2") (pinfunction "2_2") (pintype "passive"))
      (node (ref "C6") (pin "1") (pinfunction "1_1") (pintype "passive"))
      (node (ref "C8") (pin "1") (pinfunction "1_1") (pintype "passive"))
      (node (ref "D2") (pin "A") (pinfunction "A_A") (pintype "passive"))
      (node (ref "FAULT") (pin "A") (pinfunction "A_A") (pintype "passive"))
      (node (ref "IC1") (pin "3") (pinfunction "VO_3") (pintype "passive"))
      (node (ref "IC2") (pin "8") (pinfunction "V+_8") (pintype "power_in"))
      (node (ref "IC4") (pin "4") (pinfunction "/RES_4") (pintype "input"))
      (node (ref "IC4") (pin "8") (pinfunction "VCC+_8") (pintype "power_in"))
      (node (ref "IC5") (pin "5") (pinfunction "VCC_5") (pintype "power_in"))
      (node (ref "JP1") (pin "2") (pinfunction "2_2") (pintype "passive"))
      (node (ref "LIMITER") (pin "A") (pinfunction "A_A") (pintype "passive"))
      (node (ref "ON") (pin "A") (pinfunction "A_A") (pintype "passive"))
      (node (ref "R17") (pin "2") (pinfunction "2_2") (pintype "passive"))
      (node (ref "R28") (pin "1") (pinfunction "1_1") (pintype "passive"))
      (node (ref "R31") (pin "1") (pinfunction "1_1") (pintype "passive"))
      (node (ref "R39") (pin "2") (pinfunction "2_2") (pintype "passive"))
      (node (ref "V-A_METER_SUPPLY") (pin "1") (pinfunction "1_1") (pintype "passive"))
    )
    (net (code "52") (name "V-") (class "Default")
      (node (ref "C36") (pin "-") (pinfunction "-_-") (pintype "passive"))
      (node (ref "C38") (pin "2") (pinfunction "2_2") (pintype "passive"))
      (node (ref "D5") (pin "A") (pinfunction "A_A") (pintype "passive"))
      (node (ref "IC2") (pin "4") (pinfunction "V-_4") (pintype "power_in"))
    )
    (net (code "53") (name "V_FEED") (class "Default")
      (node (ref "C11") (pin "1") (pinfunction "1_1") (pintype "passive"))
      (node (ref "C19") (pin "+") (pinfunction "+_+") (pintype "passive"))
      (node (ref "C2") (pin "1") (pinfunction "1_1") (pintype "passive"))
      (node (ref "C25") (pin "+") (pinfunction "+_+") (pintype "passive"))
      (node (ref "L3") (pin "1") (pinfunction "1_1") (pintype "passive"))
      (node (ref "L4") (pin "2") (pinfunction "2_2") (pintype "passive"))
      (node (ref "R15") (pin "2") (pinfunction "2_2") (pintype "passive"))
      (node (ref "R37") (pin "A") (pinfunction "A_A") (pintype "passive"))
    )
    (net (code "54") (name "unconnected-(IC4-CON-Pad5)") (class "Default")
      (node (ref "IC4") (pin "5") (pinfunction "CON_5") (pintype "input"))
    )
    (net (code "55") (name "unconnected-(R36-S-PadS@1)") (class "Default")
      (node (ref "R36") (pin "S@1") (pinfunction "S_S@1") (pintype "passive"))
    )
    (net (code "56") (name "unconnected-(R37-S-PadS@1)") (class "Default")
      (node (ref "R37") (pin "S@1") (pinfunction "S_S@1") (pintype "passive"))
    )
    (net (code "57") (name "unconnected-(S1-P-Pad3)") (class "Default")
      (node (ref "S1") (pin "3") (pinfunction "P_3") (pintype "passive"))
    )
    (net (code "58") (name "unconnected-(S1-S-Pad1)") (class "Default")
      (node (ref "S1") (pin "1") (pinfunction "S_1") (pintype "passive"))
    )
  )
)
